# TDA2030.net
KiCad netlist of a schematic drawn in Altium Designer
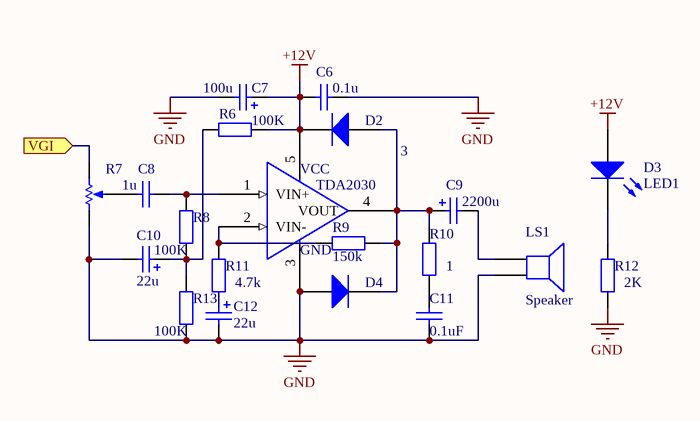
[diagram p0: 功放TDA2030.SchDoc]

(export (version "E")
  (design (tool "Eeschema 10.0.6"))
  (components
    (comp (ref "3") (value "TDA2030") (footprint "TDA2030") (libsource (lib "自制库（原理图文件）") (part "TDA2030")))
    (comp (ref "C6")
      (value "瓷片电容")
      (footprint "瓷片电容")
      (fields (field (name "ALTIUM_UNNAMED_1") "0.1u"))
      (libsource (lib "自制库（原理图文件）") (part "瓷片电容"))
    )
    (comp (ref "C7")
      (value "电解电容")
      (footprint "电解电容")
      (fields (field (name "ALTIUM_UNNAMED_1") "100u"))
      (libsource (lib "自制库（原理图文件）") (part "电解电容"))
    )
    (comp (ref "C8")
      (value "独石电容")
      (footprint "独石电容")
      (fields (field (name "ALTIUM_UNNAMED_1") "1u"))
      (libsource (lib "自制库（原理图文件）") (part "独石电容"))
    )
    (comp (ref "C9")
      (value "电解电容")
      (footprint "电解电容")
      (fields (field (name "ALTIUM_UNNAMED_1") "2200u"))
      (libsource (lib "自制库（原理图文件）") (part "电解电容"))
    )
    (comp (ref "C10")
      (value "电解电容")
      (footprint "电解电容")
      (fields (field (name "ALTIUM_UNNAMED_1") "22u"))
      (libsource (lib "自制库（原理图文件）") (part "电解电容"))
    )
    (comp (ref "C11")
      (value "瓷片电容")
      (footprint "瓷片电容")
      (fields (field (name "ALTIUM_UNNAMED_1") "0.1uF"))
      (libsource (lib "自制库（原理图文件）") (part "瓷片电容"))
    )
    (comp (ref "C12")
      (value "电解电容")
      (footprint "电解电容")
      (fields (field (name "ALTIUM_UNNAMED_1") "22u"))
      (libsource (lib "自制库（原理图文件）") (part "电解电容"))
    )
    (comp (ref "D2")
      (value "Diode 1N4007")
      (footprint "DO-41")
      (description "1 Amp General Purpose Rectifier")
      (fields (field (name "PUBLISHER") "Altium Limited"))
      (libsource (lib "Miscellaneous Devices") (part "Diode 1N4007"))
    )
    (comp (ref "D3")
      (value "LED1")
      (footprint "LED-1")
      (description "Typical RED GaAs LED")
      (fields (field (name "PUBLISHER") "Altium Limited"))
      (libsource (lib "Miscellaneous Devices") (part "LED1"))
    )
    (comp (ref "D4")
      (value "Diode 1N4007")
      (footprint "DO-41")
      (description "1 Amp General Purpose Rectifier")
      (fields (field (name "PUBLISHER") "Altium Limited"))
      (libsource (lib "Miscellaneous Devices") (part "Diode 1N4007"))
    )
    (comp (ref "LS1")
      (value "Speaker")
      (footprint "PIN2")
      (description "Loudspeaker")
      (fields (field (name "PUBLISHER") "Altium Limited"))
      (libsource (lib "Miscellaneous Devices") (part "Speaker"))
    )
    (comp (ref "R6")
      (value "100K")
      (footprint "AXIAL-0.4")
      (description "Resistor")
      (fields (field (name "Comment") "Res2") (field (name "PUBLISHER") "Altium Limited"))
      (libsource (lib "") (part "Res2_2"))
    )
    (comp (ref "R7") (value "滑阻（功放用）") (footprint "多角滑阻") (libsource (lib "自制库（原理图文件）") (part "滑阻（功放用）")))
    (comp (ref "R8")
      (value "100K")
      (footprint "AXIAL-0.4")
      (description "Resistor")
      (fields (field (name "Comment") "Res2") (field (name "PUBLISHER") "Altium Limited"))
      (libsource (lib "Miscellaneous Devices") (part "Res2"))
    )
    (comp (ref "R9")
      (value "150k")
      (footprint "AXIAL-0.4")
      (description "Resistor")
      (fields (field (name "Comment") "Res2") (field (name "PUBLISHER") "Altium Limited"))
      (libsource (lib "") (part "Res2_1"))
    )
    (comp (ref "R10")
      (value "1")
      (footprint "AXIAL-0.4")
      (description "Resistor")
      (fields (field (name "Comment") "Res2") (field (name "PUBLISHER") "Altium Limited"))
      (libsource (lib "Miscellaneous Devices") (part "Res2"))
    )
    (comp (ref "R11")
      (value "4.7k")
      (footprint "AXIAL-0.4")
      (description "Resistor")
      (fields (field (name "Comment") "Res2") (field (name "PUBLISHER") "Altium Limited"))
      (libsource (lib "Miscellaneous Devices") (part "Res2"))
    )
    (comp (ref "R12")
      (value "2K")
      (footprint "AXIAL-0.4")
      (description "Resistor")
      (fields (field (name "Comment") "Res2") (field (name "PUBLISHER") "Altium Limited"))
      (libsource (lib "Miscellaneous Devices") (part "Res2"))
    )
    (comp (ref "R13")
      (value "100K")
      (footprint "AXIAL-0.4")
      (description "Resistor")
      (fields (field (name "Comment") "Res2") (field (name "PUBLISHER") "Altium Limited"))
      (libsource (lib "Miscellaneous Devices") (part "Res2"))
    )
  )
  (nets
    (net (code "1") (name "+12V") (class "Default")
      (node (ref "3") (pin "5") (pinfunction "VCC_5") (pintype "power_in"))
      (node (ref "C6") (pin "1") (pinfunction "1_1") (pintype "passive"))
      (node (ref "C7") (pin "1") (pinfunction "1_1") (pintype "passive"))
      (node (ref "D2") (pin "2") (pinfunction "K_2") (pintype "passive"))
      (node (ref "D3") (pin "1") (pinfunction "A_1") (pintype "passive"))
      (node (ref "R6") (pin "2") (pinfunction "2_2") (pintype "passive"))
    )
    (net (code "2") (name "/VGI") (class "Default")
      (node (ref "R7") (pin "3") (pinfunction "3_3") (pintype "passive"))
    )
    (net (code "3") (name "GND") (class "Default")
      (node (ref "3") (pin "3") (pinfunction "GND_3") (pintype "power_in"))
      (node (ref "C10") (pin "2") (pinfunction "2_2") (pintype "passive"))
      (node (ref "C11") (pin "1") (pinfunction "1_1") (pintype "passive"))
      (node (ref "C12") (pin "2") (pinfunction "2_2") (pintype "passive"))
      (node (ref "C6") (pin "2") (pinfunction "2_2") (pintype "passive"))
      (node (ref "C7") (pin "2") (pinfunction "2_2") (pintype "passive"))
      (node (ref "D4") (pin "1") (pinfunction "A_1") (pintype "passive"))
      (node (ref "LS1") (pin "2") (pinfunction "2_2") (pintype "passive"))
      (node (ref "R12") (pin "1") (pinfunction "1_1") (pintype "passive"))
      (node (ref "R13") (pin "1") (pinfunction "1_1") (pintype "passive"))
      (node (ref "R7") (pin "1") (pinfunction "1_1") (pintype "passive"))
    )
    (net (code "4") (name "Net-(3-VIN+)") (class "Default")
      (node (ref "3") (pin "1") (pinfunction "VIN+_1") (pintype "input"))
      (node (ref "C8") (pin "2") (pinfunction "2_2") (pintype "passive"))
      (node (ref "R8") (pin "2") (pinfunction "2_2") (pintype "passive"))
    )
    (net (code "5") (name "Net-(3-VIN-)") (class "Default")
      (node (ref "3") (pin "2") (pinfunction "VIN-_2") (pintype "input"))
      (node (ref "R11") (pin "2") (pinfunction "2_2") (pintype "passive"))
      (node (ref "R9") (pin "2") (pinfunction "2_2") (pintype "passive"))
    )
    (net (code "6") (name "Net-(3-VOUT)") (class "Default")
      (node (ref "3") (pin "4") (pinfunction "VOUT_4") (pintype "power_in"))
      (node (ref "C9") (pin "1") (pinfunction "1_1") (pintype "passive"))
      (node (ref "D2") (pin "1") (pinfunction "A_1") (pintype "passive"))
      (node (ref "D4") (pin "2") (pinfunction "K_2") (pintype "passive"))
      (node (ref "R10") (pin "2") (pinfunction "2_2") (pintype "passive"))
      (node (ref "R9") (pin "1") (pinfunction "1_1") (pintype "passive"))
    )
    (net (code "7") (name "Net-(C9-Pad2)") (class "Default")
      (node (ref "C9") (pin "2") (pinfunction "2_2") (pintype "passive"))
      (node (ref "LS1") (pin "1") (pinfunction "1_1") (pintype "passive"))
    )
    (net (code "8") (name "Net-(C10-Pad1)") (class "Default")
      (node (ref "C10") (pin "1") (pinfunction "1_1") (pintype "passive"))
      (node (ref "R13") (pin "2") (pinfunction "2_2") (pintype "passive"))
      (node (ref "R6") (pin "1") (pinfunction "1_1") (pintype "passive"))
      (node (ref "R8") (pin "1") (pinfunction "1_1") (pintype "passive"))
    )
    (net (code "9") (name "Net-(C11-Pad2)") (class "Default")
      (node (ref "C11") (pin "2") (pinfunction "2_2") (pintype "passive"))
      (node (ref "R10") (pin "1") (pinfunction "1_1") (pintype "passive"))
    )
    (net (code "10") (name "Net-(C12-Pad1)") (class "Default")
      (node (ref "C12") (pin "1") (pinfunction "1_1") (pintype "passive"))
      (node (ref "R11") (pin "1") (pinfunction "1_1") (pintype "passive"))
    )
    (net (code "11") (name "Net-(D3-K)") (class "Default")
      (node (ref "D3") (pin "2") (pinfunction "K_2") (pintype "passive"))
      (node (ref "R12") (pin "2") (pinfunction "2_2") (pintype "passive"))
    )
    (net (code "12") (name "Net-(R7-TAP)") (class "Default")
      (node (ref "C8") (pin "1") (pinfunction "1_1") (pintype "passive"))
      (node (ref "R7") (pin "2") (pinfunction "TAP_2") (pintype "passive"))
    )
  )
)
